# SparkFun_USB_RS485_Converter.net
KiCad netlist of a schematic drawn in EAGLE
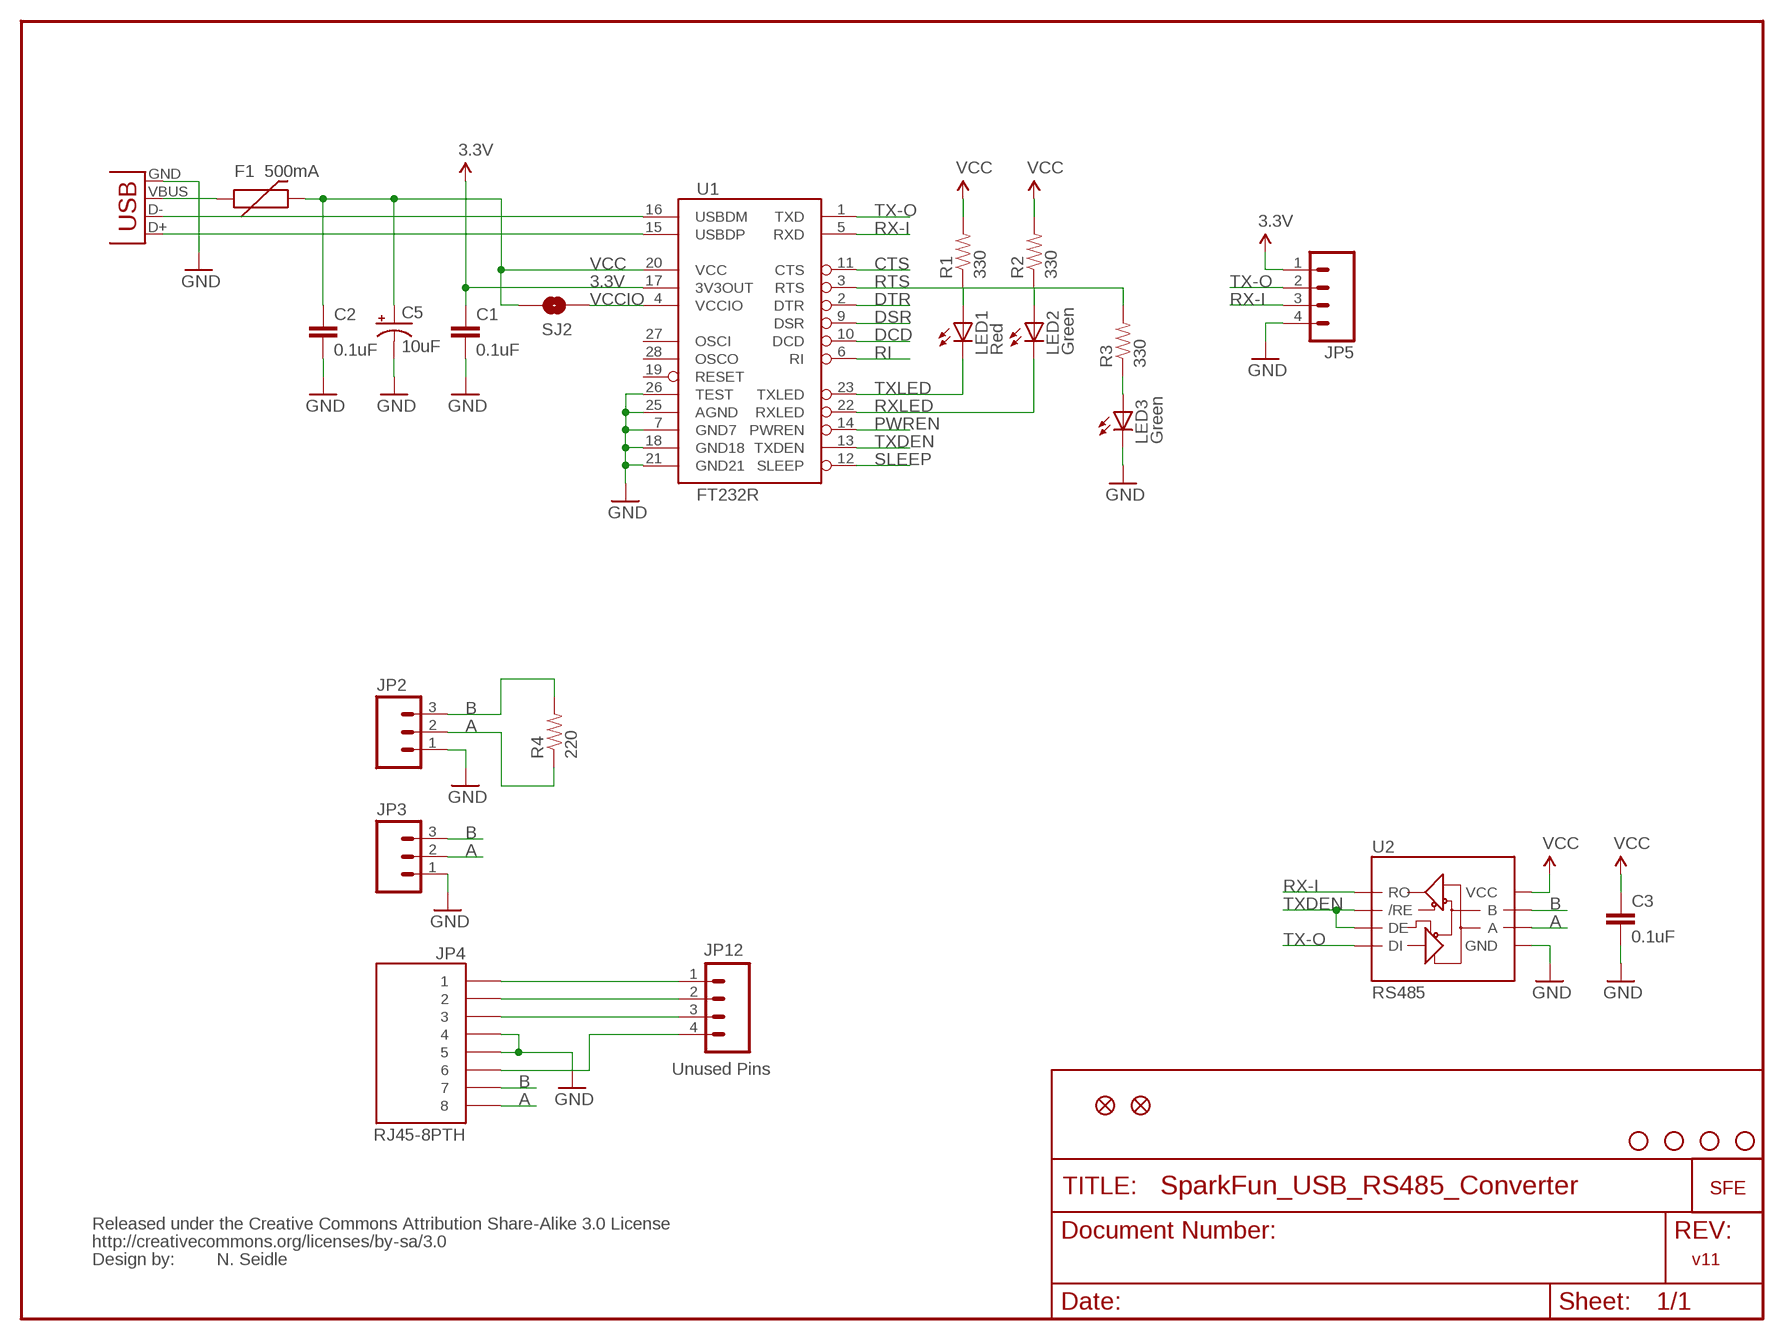
[diagram p0: schematic, sheet 1]

(export (version "E")
  (design (tool "Eeschema 10.0.6"))
  (components
    (comp (ref "C1")
      (value "0.1uF")
      (footprint "eagle-import:0402-CAP")
      (libsource (lib "eagle-import") (part "CAP0402-CAP"))
    )
    (comp (ref "C2")
      (value "0.1uF")
      (footprint "eagle-import:0402-CAP")
      (libsource (lib "eagle-import") (part "CAP0402-CAP"))
    )
    (comp (ref "C3")
      (value "0.1uF")
      (footprint "eagle-import:0402-CAP")
      (libsource (lib "eagle-import") (part "CAP0402-CAP"))
    )
    (comp (ref "C5")
      (value "10uF")
      (footprint "eagle-import:EIA3216")
      (libsource (lib "eagle-import") (part "CAP_POL1206"))
    )
    (comp (ref "F1")
      (value "500mA")
      (footprint "eagle-import:PTC-1206")
      (libsource (lib "eagle-import") (part "PTCSMD"))
    )
    (comp (ref "JP1")
      (value "STAND-OFF")
      (footprint "eagle-import:STAND-OFF")
      (libsource (lib "eagle-import") (part "STAND-OFF"))
    )
    (comp (ref "JP2")
      (value "M03SCREW")
      (footprint "eagle-import:SCREWTERMINAL-3.5MM-3")
      (libsource (lib "eagle-import") (part "M03SCREW"))
    )
    (comp (ref "JP3")
      (value "M03PTH")
      (footprint "eagle-import:1X03")
      (libsource (lib "eagle-import") (part "M03PTH"))
    )
    (comp (ref "JP4")
      (value "RJ45-8PTH")
      (footprint "eagle-import:RJ45-8")
      (libsource (lib "eagle-import") (part "RJ45-8PTH"))
    )
    (comp (ref "JP5")
      (value "M04PTH")
      (footprint "eagle-import:1X04")
      (libsource (lib "eagle-import") (part "M04PTH"))
    )
    (comp (ref "JP6")
      (value "STAND-OFF")
      (footprint "eagle-import:STAND-OFF")
      (libsource (lib "eagle-import") (part "STAND-OFF"))
    )
    (comp (ref "JP7")
      (value "STAND-OFF")
      (footprint "eagle-import:STAND-OFF")
      (libsource (lib "eagle-import") (part "STAND-OFF"))
    )
    (comp (ref "JP8")
      (value "STAND-OFF")
      (footprint "eagle-import:STAND-OFF")
      (libsource (lib "eagle-import") (part "STAND-OFF"))
    )
    (comp (ref "JP9")
      (value "FIDUCIAL1X2")
      (footprint "eagle-import:FIDUCIAL-1X2")
      (libsource (lib "eagle-import") (part "FIDUCIAL1X2"))
    )
    (comp (ref "JP10")
      (value "FIDUCIAL1X2")
      (footprint "eagle-import:FIDUCIAL-1X2")
      (libsource (lib "eagle-import") (part "FIDUCIAL1X2"))
    )
    (comp (ref "JP12")
      (value "Unused Pins")
      (footprint "eagle-import:1X04")
      (libsource (lib "eagle-import") (part "M04PTH"))
    )
    (comp (ref "LED1")
      (value "Red")
      (footprint "eagle-import:LED-0603")
      (libsource (lib "eagle-import") (part "LED0603"))
    )
    (comp (ref "LED2")
      (value "Green")
      (footprint "eagle-import:LED-0603")
      (libsource (lib "eagle-import") (part "LED0603"))
    )
    (comp (ref "LED3")
      (value "Green")
      (footprint "eagle-import:LED-0603")
      (libsource (lib "eagle-import") (part "LED0603"))
    )
    (comp (ref "R1")
      (value "330")
      (footprint "eagle-import:0402-RES")
      (libsource (lib "eagle-import") (part "RESISTOR0402-RES"))
    )
    (comp (ref "R2")
      (value "330")
      (footprint "eagle-import:0402-RES")
      (libsource (lib "eagle-import") (part "RESISTOR0402-RES"))
    )
    (comp (ref "R3")
      (value "330")
      (footprint "eagle-import:0402-RES")
      (libsource (lib "eagle-import") (part "RESISTOR0402-RES"))
    )
    (comp (ref "R4")
      (value "220")
      (footprint "eagle-import:0402-RES")
      (libsource (lib "eagle-import") (part "RESISTOR0402-RES"))
    )
    (comp (ref "SJ2")
      (value "SOLDERJUMPERNC2")
      (footprint "eagle-import:SJ_2S-NOTRACE")
      (libsource (lib "eagle-import") (part "SOLDERJUMPERNC2"))
    )
    (comp (ref "U$1")
      (value "CREATIVE_COMMONS")
      (footprint "eagle-import:CREATIVE_COMMONS")
      (libsource (lib "eagle-import") (part "CREATIVE_COMMONS"))
    )
    (comp (ref "U$2")
      (value "LOGO-SFENEW")
      (footprint "eagle-import:SFE-NEW-WEBLOGO")
      (libsource (lib "eagle-import") (part "LOGO-SFENEW"))
    )
    (comp (ref "U1")
      (value "FT232R")
      (footprint "eagle-import:SSOP28DB")
      (libsource (lib "eagle-import") (part "FT232RLSSOP"))
    )
    (comp (ref "U2")
      (value "RS485")
      (footprint "eagle-import:SO08")
      (libsource (lib "eagle-import") (part "RS485SOIC"))
    )
    (comp (ref "X2")
      (value "USBSMD")
      (footprint "eagle-import:USB-MINIB")
      (libsource (lib "eagle-import") (part "USBSMD"))
    )
  )
  (nets
    (net (code "1") (name "/A") (class "Default")
      (node (ref "JP2") (pin "2") (pinfunction "2_2") (pintype "passive"))
      (node (ref "JP3") (pin "2") (pinfunction "2_2") (pintype "passive"))
      (node (ref "JP4") (pin "8") (pinfunction "8_8") (pintype "bidirectional"))
      (node (ref "R4") (pin "1") (pinfunction "1_1") (pintype "passive"))
      (node (ref "U2") (pin "6") (pinfunction "A_6") (pintype "bidirectional"))
    )
    (net (code "2") (name "/B") (class "Default")
      (node (ref "JP2") (pin "3") (pinfunction "3_3") (pintype "passive"))
      (node (ref "JP3") (pin "3") (pinfunction "3_3") (pintype "passive"))
      (node (ref "JP4") (pin "7") (pinfunction "7_7") (pintype "bidirectional"))
      (node (ref "R4") (pin "2") (pinfunction "2_2") (pintype "passive"))
      (node (ref "U2") (pin "7") (pinfunction "B_7") (pintype "bidirectional"))
    )
    (net (code "3") (name "/CTS") (class "Default")
      (node (ref "U1") (pin "11") (pinfunction "CTS_11") (pintype "input"))
    )
    (net (code "4") (name "/DCD") (class "Default")
      (node (ref "U1") (pin "10") (pinfunction "DCD_10") (pintype "input"))
    )
    (net (code "5") (name "/DSR") (class "Default")
      (node (ref "U1") (pin "9") (pinfunction "DSR_9") (pintype "input"))
    )
    (net (code "6") (name "/DTR") (class "Default")
      (node (ref "U1") (pin "2") (pinfunction "DTR_2") (pintype "output"))
    )
    (net (code "7") (name "/PWREN") (class "Default")
      (node (ref "U1") (pin "14") (pinfunction "PWREN_14") (pintype "input"))
    )
    (net (code "8") (name "/RI") (class "Default")
      (node (ref "U1") (pin "6") (pinfunction "RI_6") (pintype "input"))
    )
    (net (code "9") (name "/RTS") (class "Default")
      (node (ref "R3") (pin "2") (pinfunction "2_2") (pintype "passive"))
      (node (ref "U1") (pin "3") (pinfunction "RTS_3") (pintype "output"))
    )
    (net (code "10") (name "/RX-I") (class "Default")
      (node (ref "JP5") (pin "3") (pinfunction "3_3") (pintype "passive"))
      (node (ref "U1") (pin "5") (pinfunction "RXD_5") (pintype "input"))
      (node (ref "U2") (pin "1") (pinfunction "RO_1") (pintype "bidirectional"))
    )
    (net (code "11") (name "/RXLED") (class "Default")
      (node (ref "LED2") (pin "C") (pinfunction "C_C") (pintype "passive"))
      (node (ref "U1") (pin "22") (pinfunction "RXLED_22") (pintype "input"))
    )
    (net (code "12") (name "/SLEEP") (class "Default")
      (node (ref "U1") (pin "12") (pinfunction "SLEEP_12") (pintype "input"))
    )
    (net (code "13") (name "/TX-O") (class "Default")
      (node (ref "JP5") (pin "2") (pinfunction "2_2") (pintype "passive"))
      (node (ref "U1") (pin "1") (pinfunction "TXD_1") (pintype "output"))
      (node (ref "U2") (pin "4") (pinfunction "DI_4") (pintype "bidirectional"))
    )
    (net (code "14") (name "/TXDEN") (class "Default")
      (node (ref "U1") (pin "13") (pinfunction "TXDEN_13") (pintype "input"))
      (node (ref "U2") (pin "2") (pinfunction "/RE_2") (pintype "bidirectional"))
      (node (ref "U2") (pin "3") (pinfunction "DE_3") (pintype "bidirectional"))
    )
    (net (code "15") (name "/TXLED") (class "Default")
      (node (ref "LED1") (pin "C") (pinfunction "C_C") (pintype "passive"))
      (node (ref "U1") (pin "23") (pinfunction "TXLED_23") (pintype "input"))
    )
    (net (code "16") (name "/VCCIO") (class "Default")
      (node (ref "SJ2") (pin "1") (pinfunction "1_1") (pintype "passive"))
      (node (ref "U1") (pin "4") (pinfunction "VCCIO_4") (pintype "power_in"))
    )
    (net (code "17") (name "3.3V") (class "Default")
      (node (ref "C1") (pin "1") (pinfunction "1_1") (pintype "passive"))
      (node (ref "JP5") (pin "1") (pinfunction "1_1") (pintype "passive"))
      (node (ref "U1") (pin "17") (pinfunction "3V3OUT_17") (pintype "output"))
    )
    (net (code "18") (name "GND") (class "Default")
      (node (ref "C1") (pin "2") (pinfunction "2_2") (pintype "passive"))
      (node (ref "C2") (pin "2") (pinfunction "2_2") (pintype "passive"))
      (node (ref "C3") (pin "2") (pinfunction "2_2") (pintype "passive"))
      (node (ref "C5") (pin "C") (pinfunction "-_C") (pintype "passive"))
      (node (ref "JP2") (pin "1") (pinfunction "1_1") (pintype "passive"))
      (node (ref "JP3") (pin "1") (pinfunction "1_1") (pintype "passive"))
      (node (ref "JP4") (pin "4") (pinfunction "4_4") (pintype "bidirectional"))
      (node (ref "JP4") (pin "5") (pinfunction "5_5") (pintype "bidirectional"))
      (node (ref "JP5") (pin "4") (pinfunction "4_4") (pintype "passive"))
      (node (ref "LED3") (pin "C") (pinfunction "C_C") (pintype "passive"))
      (node (ref "U1") (pin "18") (pinfunction "GND18_18") (pintype "power_in"))
      (node (ref "U1") (pin "21") (pinfunction "GND21_21") (pintype "power_in"))
      (node (ref "U1") (pin "25") (pinfunction "AGND_25") (pintype "power_in"))
      (node (ref "U1") (pin "26") (pinfunction "TEST_26") (pintype "input"))
      (node (ref "U1") (pin "7") (pinfunction "GND7_7") (pintype "power_in"))
      (node (ref "U2") (pin "5") (pinfunction "GND_5") (pintype "bidirectional"))
      (node (ref "X2") (pin "GND") (pinfunction "GND_GND") (pintype "bidirectional"))
    )
    (net (code "19") (name "Net-(F1-Pad1)") (class "Default")
      (node (ref "F1") (pin "1") (pinfunction "1_1") (pintype "bidirectional"))
      (node (ref "X2") (pin "VBUS") (pinfunction "VBUS_VBUS") (pintype "bidirectional"))
    )
    (net (code "20") (name "Net-(JP12-Pad1)") (class "Default")
      (node (ref "JP12") (pin "1") (pinfunction "1_1") (pintype "passive"))
      (node (ref "JP4") (pin "1") (pinfunction "1_1") (pintype "bidirectional"))
    )
    (net (code "21") (name "Net-(JP12-Pad2)") (class "Default")
      (node (ref "JP12") (pin "2") (pinfunction "2_2") (pintype "passive"))
      (node (ref "JP4") (pin "2") (pinfunction "2_2") (pintype "bidirectional"))
    )
    (net (code "22") (name "Net-(JP12-Pad3)") (class "Default")
      (node (ref "JP12") (pin "3") (pinfunction "3_3") (pintype "passive"))
      (node (ref "JP4") (pin "3") (pinfunction "3_3") (pintype "bidirectional"))
    )
    (net (code "23") (name "Net-(JP12-Pad4)") (class "Default")
      (node (ref "JP12") (pin "4") (pinfunction "4_4") (pintype "passive"))
      (node (ref "JP4") (pin "6") (pinfunction "6_6") (pintype "bidirectional"))
    )
    (net (code "24") (name "Net-(LED1-PadA)") (class "Default")
      (node (ref "LED1") (pin "A") (pinfunction "A_A") (pintype "passive"))
      (node (ref "R1") (pin "1") (pinfunction "1_1") (pintype "passive"))
    )
    (net (code "25") (name "Net-(LED2-PadA)") (class "Default")
      (node (ref "LED2") (pin "A") (pinfunction "A_A") (pintype "passive"))
      (node (ref "R2") (pin "1") (pinfunction "1_1") (pintype "passive"))
    )
    (net (code "26") (name "Net-(LED3-PadA)") (class "Default")
      (node (ref "LED3") (pin "A") (pinfunction "A_A") (pintype "passive"))
      (node (ref "R3") (pin "1") (pinfunction "1_1") (pintype "passive"))
    )
    (net (code "27") (name "Net-(U1-USBDM)") (class "Default")
      (node (ref "U1") (pin "16") (pinfunction "USBDM_16") (pintype "bidirectional"))
      (node (ref "X2") (pin "D-") (pinfunction "D-_D-") (pintype "bidirectional"))
    )
    (net (code "28") (name "Net-(U1-USBDP)") (class "Default")
      (node (ref "U1") (pin "15") (pinfunction "USBDP_15") (pintype "bidirectional"))
      (node (ref "X2") (pin "D+") (pinfunction "D+_D+") (pintype "bidirectional"))
    )
    (net (code "29") (name "VCC") (class "Default")
      (node (ref "C2") (pin "1") (pinfunction "1_1") (pintype "passive"))
      (node (ref "C3") (pin "1") (pinfunction "1_1") (pintype "passive"))
      (node (ref "C5") (pin "A") (pinfunction "+_A") (pintype "passive"))
      (node (ref "F1") (pin "2") (pinfunction "2_2") (pintype "bidirectional"))
      (node (ref "R1") (pin "2") (pinfunction "2_2") (pintype "passive"))
      (node (ref "R2") (pin "2") (pinfunction "2_2") (pintype "passive"))
      (node (ref "SJ2") (pin "2") (pinfunction "2_2") (pintype "passive"))
      (node (ref "U1") (pin "20") (pinfunction "VCC_20") (pintype "power_in"))
      (node (ref "U2") (pin "8") (pinfunction "VCC_8") (pintype "bidirectional"))
    )
    (net (code "30") (name "unconnected-(U1-OSCI-Pad27)") (class "Default")
      (node (ref "U1") (pin "27") (pinfunction "OSCI_27") (pintype "input"))
    )
    (net (code "31") (name "unconnected-(U1-OSCO-Pad28)") (class "Default")
      (node (ref "U1") (pin "28") (pinfunction "OSCO_28") (pintype "output"))
    )
    (net (code "32") (name "unconnected-(U1-RESET-Pad19)") (class "Default")
      (node (ref "U1") (pin "19") (pinfunction "RESET_19") (pintype "input"))
    )
  )
)
